# expansion_board.net
KiCad netlist of a schematic drawn in EAGLE
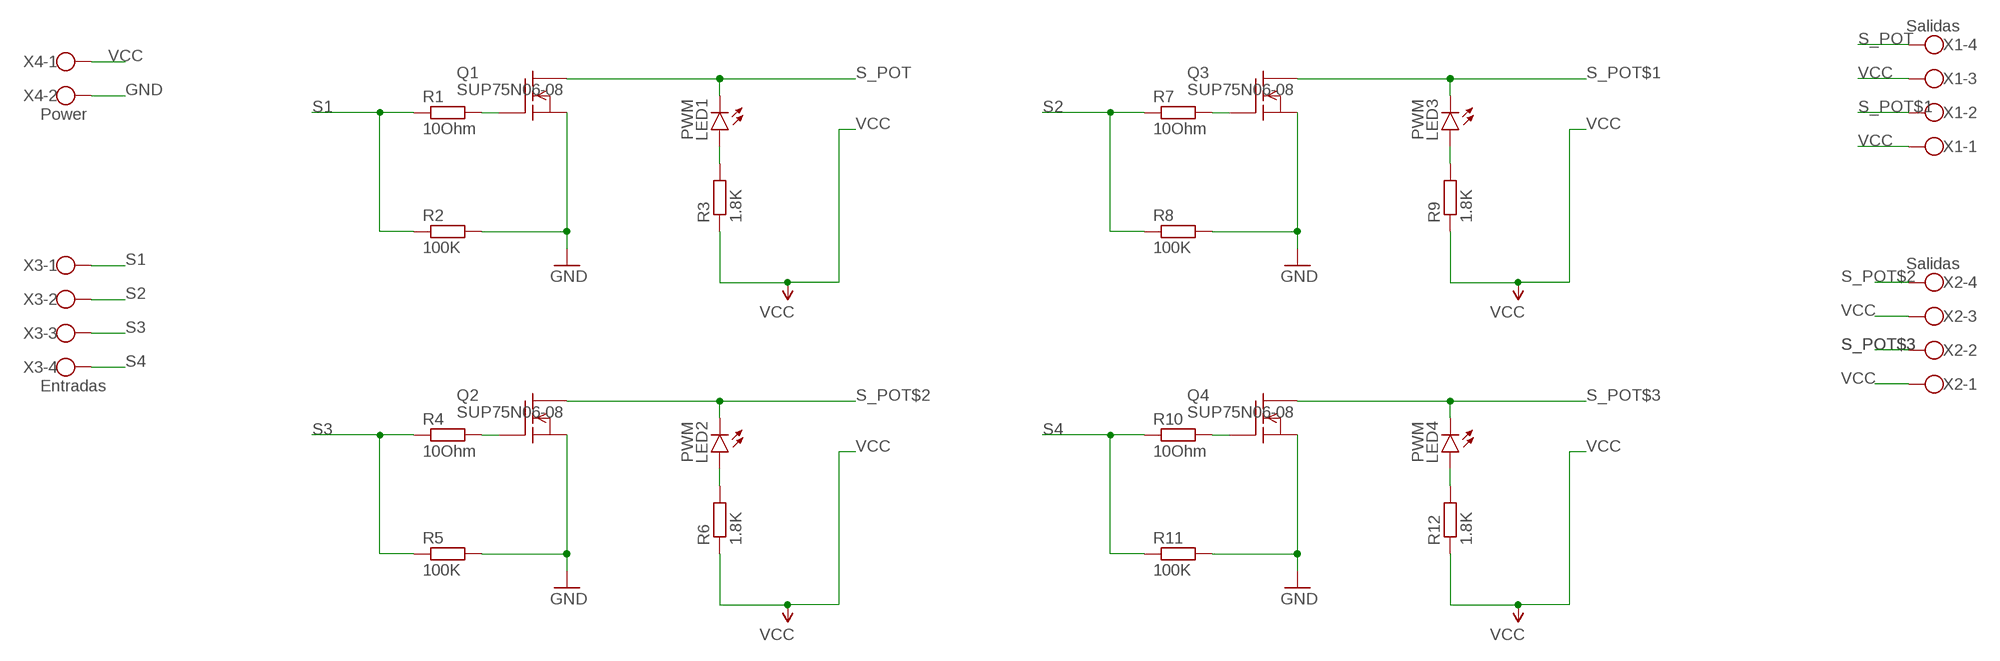
[diagram p0: schematic, sheet 1]

(export (version "E")
  (design (tool "Eeschema 10.0.6"))
  (components
    (comp (ref "LED1")
      (value "PWM")
      (footprint "eagle-import:LED5MM")
      (libsource (lib "eagle-import") (part "LED5MM"))
    )
    (comp (ref "LED2")
      (value "PWM")
      (footprint "eagle-import:LED5MM")
      (libsource (lib "eagle-import") (part "LED5MM"))
    )
    (comp (ref "LED3")
      (value "PWM")
      (footprint "eagle-import:LED5MM")
      (libsource (lib "eagle-import") (part "LED5MM"))
    )
    (comp (ref "LED4")
      (value "PWM")
      (footprint "eagle-import:LED5MM")
      (libsource (lib "eagle-import") (part "LED5MM"))
    )
    (comp (ref "Q1")
      (value "SUP75N06-08")
      (footprint "eagle-import:TO220")
      (libsource (lib "eagle-import") (part "SUP75N06-08"))
    )
    (comp (ref "Q2")
      (value "SUP75N06-08")
      (footprint "eagle-import:TO220")
      (libsource (lib "eagle-import") (part "SUP75N06-08"))
    )
    (comp (ref "Q3")
      (value "SUP75N06-08")
      (footprint "eagle-import:TO220")
      (libsource (lib "eagle-import") (part "SUP75N06-08"))
    )
    (comp (ref "Q4")
      (value "SUP75N06-08")
      (footprint "eagle-import:TO220")
      (libsource (lib "eagle-import") (part "SUP75N06-08"))
    )
    (comp (ref "R1")
      (value "10Ohm")
      (footprint "eagle-import:0207_7")
      (libsource (lib "eagle-import") (part "R-EU_0207/7"))
    )
    (comp (ref "R2")
      (value "100K")
      (footprint "eagle-import:0207_7")
      (libsource (lib "eagle-import") (part "R-EU_0207/7"))
    )
    (comp (ref "R3")
      (value "1.8K")
      (footprint "eagle-import:0207_7")
      (libsource (lib "eagle-import") (part "R-EU_0207/7"))
    )
    (comp (ref "R4")
      (value "10Ohm")
      (footprint "eagle-import:0207_7")
      (libsource (lib "eagle-import") (part "R-EU_0207/7"))
    )
    (comp (ref "R5")
      (value "100K")
      (footprint "eagle-import:0207_7")
      (libsource (lib "eagle-import") (part "R-EU_0207/7"))
    )
    (comp (ref "R6")
      (value "1.8K")
      (footprint "eagle-import:0207_7")
      (libsource (lib "eagle-import") (part "R-EU_0207/7"))
    )
    (comp (ref "R7")
      (value "10Ohm")
      (footprint "eagle-import:0207_7")
      (libsource (lib "eagle-import") (part "R-EU_0207/7"))
    )
    (comp (ref "R8")
      (value "100K")
      (footprint "eagle-import:0207_7")
      (libsource (lib "eagle-import") (part "R-EU_0207/7"))
    )
    (comp (ref "R9")
      (value "1.8K")
      (footprint "eagle-import:0207_7")
      (libsource (lib "eagle-import") (part "R-EU_0207/7"))
    )
    (comp (ref "R10")
      (value "10Ohm")
      (footprint "eagle-import:0207_7")
      (libsource (lib "eagle-import") (part "R-EU_0207/7"))
    )
    (comp (ref "R11")
      (value "100K")
      (footprint "eagle-import:0207_7")
      (libsource (lib "eagle-import") (part "R-EU_0207/7"))
    )
    (comp (ref "R12")
      (value "1.8K")
      (footprint "eagle-import:0207_7")
      (libsource (lib "eagle-import") (part "R-EU_0207/7"))
    )
    (comp (ref "X1")
      (value "Salidas")
      (footprint "eagle-import:W237-4")
      (libsource (lib "eagle-import") (part "W237-4"))
    )
    (comp (ref "X2")
      (value "Salidas")
      (footprint "eagle-import:W237-4")
      (libsource (lib "eagle-import") (part "W237-4"))
    )
    (comp (ref "X3")
      (value "Entradas")
      (footprint "eagle-import:W237-4")
      (libsource (lib "eagle-import") (part "W237-4"))
    )
    (comp (ref "X4")
      (value "Power")
      (footprint "eagle-import:W237-102")
      (fields (field (name "MPN") "237-102"))
      (libsource (lib "eagle-import") (part "W237-102"))
    )
  )
  (nets
    (net (code "1") (name "/S1") (class "Default")
      (node (ref "R1") (pin "1") (pinfunction "1_1") (pintype "passive"))
      (node (ref "R2") (pin "1") (pinfunction "1_1") (pintype "passive"))
      (node (ref "X3") (pin "1") (pinfunction "KL_1") (pintype "passive"))
    )
    (net (code "2") (name "/S2") (class "Default")
      (node (ref "R7") (pin "1") (pinfunction "1_1") (pintype "passive"))
      (node (ref "R8") (pin "1") (pinfunction "1_1") (pintype "passive"))
      (node (ref "X3") (pin "2") (pinfunction "KL_2") (pintype "passive"))
    )
    (net (code "3") (name "/S3") (class "Default")
      (node (ref "R4") (pin "1") (pinfunction "1_1") (pintype "passive"))
      (node (ref "R5") (pin "1") (pinfunction "1_1") (pintype "passive"))
      (node (ref "X3") (pin "3") (pinfunction "KL_3") (pintype "passive"))
    )
    (net (code "4") (name "/S4") (class "Default")
      (node (ref "R10") (pin "1") (pinfunction "1_1") (pintype "passive"))
      (node (ref "R11") (pin "1") (pinfunction "1_1") (pintype "passive"))
      (node (ref "X3") (pin "4") (pinfunction "KL_4") (pintype "passive"))
    )
    (net (code "5") (name "/S_POT") (class "Default")
      (node (ref "LED1") (pin "K") (pinfunction "C_K") (pintype "passive"))
      (node (ref "Q1") (pin "2") (pinfunction "D_2") (pintype "passive"))
      (node (ref "X1") (pin "4") (pinfunction "KL_4") (pintype "passive"))
    )
    (net (code "6") (name "/S_POT$1") (class "Default")
      (node (ref "LED3") (pin "K") (pinfunction "C_K") (pintype "passive"))
      (node (ref "Q3") (pin "2") (pinfunction "D_2") (pintype "passive"))
      (node (ref "X1") (pin "2") (pinfunction "KL_2") (pintype "passive"))
    )
    (net (code "7") (name "/S_POT$2") (class "Default")
      (node (ref "LED2") (pin "K") (pinfunction "C_K") (pintype "passive"))
      (node (ref "Q2") (pin "2") (pinfunction "D_2") (pintype "passive"))
      (node (ref "X2") (pin "4") (pinfunction "KL_4") (pintype "passive"))
    )
    (net (code "8") (name "/S_POT$3") (class "Default")
      (node (ref "LED4") (pin "K") (pinfunction "C_K") (pintype "passive"))
      (node (ref "Q4") (pin "2") (pinfunction "D_2") (pintype "passive"))
      (node (ref "X2") (pin "2") (pinfunction "KL_2") (pintype "passive"))
    )
    (net (code "9") (name "GND") (class "Default")
      (node (ref "Q1") (pin "3") (pinfunction "S_3") (pintype "passive"))
      (node (ref "Q2") (pin "3") (pinfunction "S_3") (pintype "passive"))
      (node (ref "Q3") (pin "3") (pinfunction "S_3") (pintype "passive"))
      (node (ref "Q4") (pin "3") (pinfunction "S_3") (pintype "passive"))
      (node (ref "R11") (pin "2") (pinfunction "2_2") (pintype "passive"))
      (node (ref "R2") (pin "2") (pinfunction "2_2") (pintype "passive"))
      (node (ref "R5") (pin "2") (pinfunction "2_2") (pintype "passive"))
      (node (ref "R8") (pin "2") (pinfunction "2_2") (pintype "passive"))
      (node (ref "X4") (pin "2") (pinfunction "KL_2") (pintype "passive"))
    )
    (net (code "10") (name "Net-(LED1-PadA)") (class "Default")
      (node (ref "LED1") (pin "A") (pinfunction "A_A") (pintype "passive"))
      (node (ref "R3") (pin "2") (pinfunction "2_2") (pintype "passive"))
    )
    (net (code "11") (name "Net-(LED2-PadA)") (class "Default")
      (node (ref "LED2") (pin "A") (pinfunction "A_A") (pintype "passive"))
      (node (ref "R6") (pin "2") (pinfunction "2_2") (pintype "passive"))
    )
    (net (code "12") (name "Net-(LED3-PadA)") (class "Default")
      (node (ref "LED3") (pin "A") (pinfunction "A_A") (pintype "passive"))
      (node (ref "R9") (pin "2") (pinfunction "2_2") (pintype "passive"))
    )
    (net (code "13") (name "Net-(LED4-PadA)") (class "Default")
      (node (ref "LED4") (pin "A") (pinfunction "A_A") (pintype "passive"))
      (node (ref "R12") (pin "2") (pinfunction "2_2") (pintype "passive"))
    )
    (net (code "14") (name "Net-(Q1-G)") (class "Default")
      (node (ref "Q1") (pin "1") (pinfunction "G_1") (pintype "passive"))
      (node (ref "R1") (pin "2") (pinfunction "2_2") (pintype "passive"))
    )
    (net (code "15") (name "Net-(Q2-G)") (class "Default")
      (node (ref "Q2") (pin "1") (pinfunction "G_1") (pintype "passive"))
      (node (ref "R4") (pin "2") (pinfunction "2_2") (pintype "passive"))
    )
    (net (code "16") (name "Net-(Q3-G)") (class "Default")
      (node (ref "Q3") (pin "1") (pinfunction "G_1") (pintype "passive"))
      (node (ref "R7") (pin "2") (pinfunction "2_2") (pintype "passive"))
    )
    (net (code "17") (name "Net-(Q4-G)") (class "Default")
      (node (ref "Q4") (pin "1") (pinfunction "G_1") (pintype "passive"))
      (node (ref "R10") (pin "2") (pinfunction "2_2") (pintype "passive"))
    )
    (net (code "18") (name "VCC") (class "Default")
      (node (ref "R12") (pin "1") (pinfunction "1_1") (pintype "passive"))
      (node (ref "R3") (pin "1") (pinfunction "1_1") (pintype "passive"))
      (node (ref "R6") (pin "1") (pinfunction "1_1") (pintype "passive"))
      (node (ref "R9") (pin "1") (pinfunction "1_1") (pintype "passive"))
      (node (ref "X1") (pin "1") (pinfunction "KL_1") (pintype "passive"))
      (node (ref "X1") (pin "3") (pinfunction "KL_3") (pintype "passive"))
      (node (ref "X2") (pin "1") (pinfunction "KL_1") (pintype "passive"))
      (node (ref "X2") (pin "3") (pinfunction "KL_3") (pintype "passive"))
      (node (ref "X4") (pin "1") (pinfunction "KL_1") (pintype "passive"))
    )
  )
)
